# oresat-proto-card-7.net
KiCad netlist of a schematic drawn in EAGLE
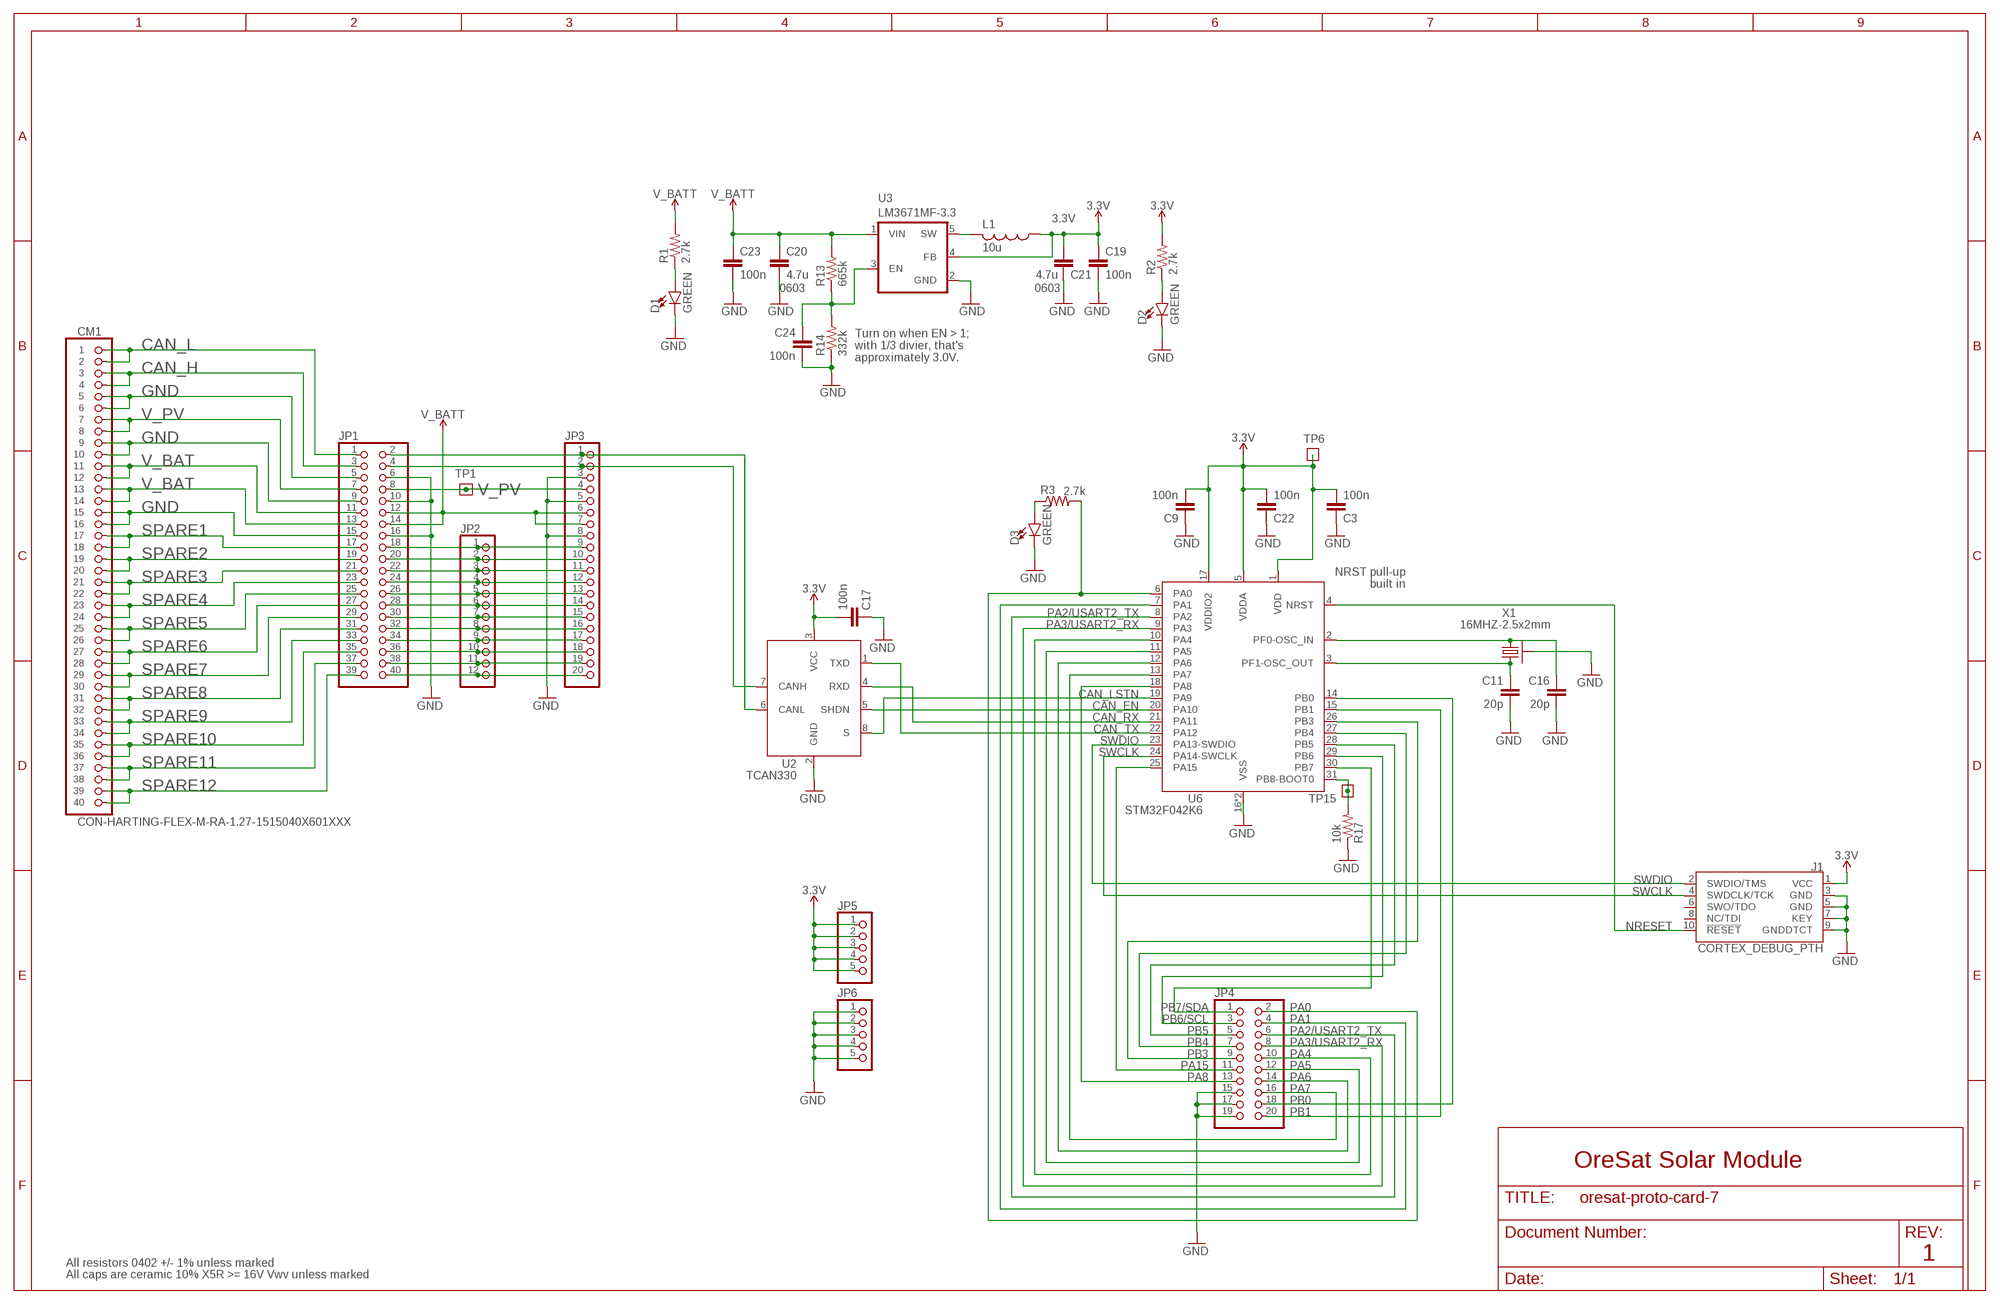
[diagram p0: schematic, sheet 1]

(export (version "E")
  (design (tool "Eeschema 10.0.6"))
  (components
    (comp (ref "C3")
      (value "100n")
      (footprint "eagle-import:.0402-B-NOSILK")
      (fields (field (name "MFR") "Samsung") (field (name "MPN") "CL05B104KO5NNNC"))
      (libsource (lib "eagle-import") (part "C-EU0402-B-NOSILK"))
    )
    (comp (ref "C9")
      (value "100n")
      (footprint "eagle-import:.0402-B-NOSILK")
      (fields (field (name "MFR") "Samsung") (field (name "MPN") "CL05B104KO5NNNC"))
      (libsource (lib "eagle-import") (part "C-EU0402-B-NOSILK"))
    )
    (comp (ref "C11")
      (value "20p")
      (footprint "eagle-import:.0402-B-NOSILK")
      (fields (field (name "MFR") "Samsung") (field (name "MPN") "CL05C200JB51PNC"))
      (libsource (lib "eagle-import") (part "C-EU0402-B-NOSILK"))
    )
    (comp (ref "C16")
      (value "20p")
      (footprint "eagle-import:.0402-B-NOSILK")
      (fields (field (name "MFR") "Samsung") (field (name "MPN") "CL05C200JB51PNC"))
      (libsource (lib "eagle-import") (part "C-EU0402-B-NOSILK"))
    )
    (comp (ref "C17")
      (value "100n")
      (footprint "eagle-import:.0402-B-NOSILK")
      (fields (field (name "MFR") "Samsung") (field (name "MPN") "CL05B104KO5NNNC"))
      (libsource (lib "eagle-import") (part "C-EU0402-B-NOSILK"))
    )
    (comp (ref "C19")
      (value "100n")
      (footprint "eagle-import:.0402-B-NOSILK")
      (fields (field (name "MFR") "Samsung") (field (name "MPN") "CL05B104KO5NNNC"))
      (libsource (lib "eagle-import") (part "C-EU0402-B-NOSILK"))
    )
    (comp (ref "C20")
      (value "4.7u")
      (footprint "eagle-import:C0603")
      (fields (field (name "MFR") "Samsung") (field (name "MPN") "CL05B104KO5NNNC"))
      (libsource (lib "eagle-import") (part "C-EUC0603"))
    )
    (comp (ref "C21")
      (value "4.7u")
      (footprint "eagle-import:C0603")
      (fields (field (name "MFR") "Samsung") (field (name "MPN") "CL05B104KO5NNNC"))
      (libsource (lib "eagle-import") (part "C-EUC0603"))
    )
    (comp (ref "C22")
      (value "100n")
      (footprint "eagle-import:.0402-B-NOSILK")
      (fields (field (name "MFR") "Samsung") (field (name "MPN") "CL05B104KO5NNNC"))
      (libsource (lib "eagle-import") (part "C-EU0402-B-NOSILK"))
    )
    (comp (ref "C23")
      (value "100n")
      (footprint "eagle-import:.0402-B-NOSILK")
      (fields (field (name "MFR") "Samsung") (field (name "MPN") "CL05B104KO5NNNC"))
      (libsource (lib "eagle-import") (part "C-EU0402-B-NOSILK"))
    )
    (comp (ref "C24")
      (value "100n")
      (footprint "eagle-import:.0402-B-NOSILK")
      (fields (field (name "MFR") "Samsung") (field (name "MPN") "CL05B104KO5NNNC"))
      (libsource (lib "eagle-import") (part "C-EU0402-B-NOSILK"))
    )
    (comp (ref "CM1")
      (value "CON-HARTING-FLEX-M-RA-1.27-1515040X601XXX")
      (footprint "eagle-import:CON-1.27-M-RA-HARTING-1515040X601XXX")
      (libsource (lib "eagle-import") (part "CON-HARTING-FLEX-M-RA-1.27-1515040X601XXX"))
    )
    (comp (ref "D1")
      (value "GREEN")
      (footprint "eagle-import:LED-0603")
      (libsource (lib "eagle-import") (part "LED-GREEN0603"))
    )
    (comp (ref "D2")
      (value "GREEN")
      (footprint "eagle-import:LED-0603")
      (libsource (lib "eagle-import") (part "LED-GREEN0603"))
    )
    (comp (ref "D3")
      (value "GREEN")
      (footprint "eagle-import:LED-0603")
      (libsource (lib "eagle-import") (part "LED-GREEN0603"))
    )
    (comp (ref "J1")
      (value "CORTEX_DEBUG_PTH")
      (footprint "eagle-import:2X5-PTH-1.27MM")
      (libsource (lib "eagle-import") (part "CORTEX_DEBUG_PTH"))
    )
    (comp (ref "JP1")
      (value "PINHD-2X20")
      (footprint "eagle-import:2X20")
      (libsource (lib "eagle-import") (part "PINHD-2X20"))
    )
    (comp (ref "JP2")
      (value "PINHD-1X12")
      (footprint "eagle-import:1X12")
      (libsource (lib "eagle-import") (part "PINHD-1X12"))
    )
    (comp (ref "JP3")
      (value "PINHD-1X20")
      (footprint "eagle-import:1X20")
      (libsource (lib "eagle-import") (part "PINHD-1X20"))
    )
    (comp (ref "JP4")
      (value "PINHD-2X10")
      (footprint "eagle-import:2X10")
      (libsource (lib "eagle-import") (part "PINHD-2X10"))
    )
    (comp (ref "JP5")
      (value "PINHD-1X5")
      (footprint "eagle-import:1X05")
      (libsource (lib "eagle-import") (part "PINHD-1X5"))
    )
    (comp (ref "JP6")
      (value "PINHD-1X5")
      (footprint "eagle-import:1X05")
      (libsource (lib "eagle-import") (part "PINHD-1X5"))
    )
    (comp (ref "L1")
      (value "10u")
      (footprint "eagle-import:L2012C")
      (fields (field (name "MFR") "Taiyo Yuden") (field (name "MPN") "CB2012T100KR"))
      (libsource (lib "eagle-import") (part "L-USL2012C"))
    )
    (comp (ref "R1")
      (value "2.7k")
      (footprint "eagle-import:.0402-B-NOSILK")
      (fields (field (name "MFR") "Samsung") (field (name "MPN") "RC1005F6653CS"))
      (libsource (lib "eagle-import") (part "R-US_0402-B-NOSILK"))
    )
    (comp (ref "R2")
      (value "2.7k")
      (footprint "eagle-import:.0402-B-NOSILK")
      (fields (field (name "MFR") "Samsung") (field (name "MPN") "RC1005F6653CS"))
      (libsource (lib "eagle-import") (part "R-US_0402-B-NOSILK"))
    )
    (comp (ref "R3")
      (value "2.7k")
      (footprint "eagle-import:.0402-B-NOSILK")
      (fields (field (name "MFR") "Samsung") (field (name "MPN") "RC1005F6653CS"))
      (libsource (lib "eagle-import") (part "R-US_0402-B-NOSILK"))
    )
    (comp (ref "R13")
      (value "665k")
      (footprint "eagle-import:.0402-B-NOSILK")
      (fields (field (name "MFR") "Samsung") (field (name "MPN") "RC1005F6653CS"))
      (libsource (lib "eagle-import") (part "R-US_0402-B-NOSILK"))
    )
    (comp (ref "R14")
      (value "332k")
      (footprint "eagle-import:.0402-B-NOSILK")
      (fields (field (name "MFR") "Samsung") (field (name "MPN") "RC1005F3323CS"))
      (libsource (lib "eagle-import") (part "R-US_0402-B-NOSILK"))
    )
    (comp (ref "R17")
      (value "10k")
      (footprint "eagle-import:.0402-B-NOSILK")
      (fields (field (name "MFR") "Samsung") (field (name "MPN") "RC1005F6653CS"))
      (libsource (lib "eagle-import") (part "R-US_0402-B-NOSILK"))
    )
    (comp (ref "TP1")
      (value "TEST-POINT")
      (footprint "eagle-import:2MM-TEST-POINT")
      (libsource (lib "eagle-import") (part "TEST-POINT"))
    )
    (comp (ref "TP6")
      (value "TEST-POINT")
      (footprint "eagle-import:2MM-TEST-POINT")
      (libsource (lib "eagle-import") (part "TEST-POINT"))
    )
    (comp (ref "TP15")
      (value "TEST-POINT")
      (footprint "eagle-import:2MM-TEST-POINT")
      (libsource (lib "eagle-import") (part "TEST-POINT"))
    )
    (comp (ref "U2")
      (value "TCAN330")
      (footprint "eagle-import:SOT23-8_TI-DCN")
      (fields (field (name "MFR") "Texas Instruments") (field (name "MPN") "TCAN330GDCNT"))
      (libsource (lib "eagle-import") (part "TCAN330"))
    )
    (comp (ref "U3")
      (value "LM3671MF-3.3")
      (footprint "eagle-import:SOT23-5")
      (fields (field (name "MFR") "TI") (field (name "MPN") "LM3671MF-3.3/NOPB"))
      (libsource (lib "eagle-import") (part "LM3761"))
    )
    (comp (ref "U6")
      (value "STM32F042K6")
      (footprint "eagle-import:QFP32-7X7")
      (fields (field (name "MFR") "STMicroelectronics") (field (name "MPN") "STM32F042K6T7"))
      (libsource (lib "eagle-import") (part "STM32F042K6"))
    )
    (comp (ref "X1")
      (value "16MHZ-2.5x2mm")
      (footprint "eagle-import:CRYSTAL_2.5X2")
      (fields (field (name "MFR") "ECS Inc.") (field (name "MPN") "ECS-160-10-36Q-ES-TR"))
      (libsource (lib "eagle-import") (part "CRYSTAL-WITH-GND"))
    )
  )
  (nets
    (net (code "1") (name "/CAN_EN") (class "Default")
      (node (ref "U2") (pin "5") (pinfunction "SHDN_5") (pintype "input"))
      (node (ref "U6") (pin "20") (pinfunction "PA10_20") (pintype "bidirectional"))
    )
    (net (code "2") (name "/CAN_H") (class "Default")
      (node (ref "CM1") (pin "3") (pinfunction "3_3") (pintype "passive"))
      (node (ref "CM1") (pin "4") (pinfunction "4_4") (pintype "passive"))
      (node (ref "JP1") (pin "3") (pinfunction "3_3") (pintype "passive"))
    )
    (net (code "3") (name "/CAN_L") (class "Default")
      (node (ref "CM1") (pin "1") (pinfunction "1_1") (pintype "passive"))
      (node (ref "CM1") (pin "2") (pinfunction "2_2") (pintype "passive"))
      (node (ref "JP1") (pin "1") (pinfunction "1_1") (pintype "passive"))
    )
    (net (code "4") (name "/CAN_LSTN") (class "Default")
      (node (ref "U2") (pin "8") (pinfunction "S_8") (pintype "input"))
      (node (ref "U6") (pin "19") (pinfunction "PA9_19") (pintype "bidirectional"))
    )
    (net (code "5") (name "/CAN_RX") (class "Default")
      (node (ref "U2") (pin "4") (pinfunction "RXD_4") (pintype "output"))
      (node (ref "U6") (pin "21") (pinfunction "PA11_21") (pintype "bidirectional"))
    )
    (net (code "6") (name "/CAN_TX") (class "Default")
      (node (ref "U2") (pin "1") (pinfunction "TXD_1") (pintype "input"))
      (node (ref "U6") (pin "22") (pinfunction "PA12_22") (pintype "bidirectional"))
    )
    (net (code "7") (name "/NRESET") (class "Default")
      (node (ref "J1") (pin "10") (pinfunction "~{RESET}_10") (pintype "bidirectional"))
      (node (ref "U6") (pin "4") (pinfunction "NRST_4") (pintype "bidirectional"))
    )
    (net (code "8") (name "/PA0") (class "Default")
      (node (ref "JP4") (pin "2") (pinfunction "2_2") (pintype "passive"))
      (node (ref "R3") (pin "2") (pinfunction "2_2") (pintype "passive"))
      (node (ref "U6") (pin "6") (pinfunction "PA0_6") (pintype "bidirectional"))
    )
    (net (code "9") (name "/PA1") (class "Default")
      (node (ref "JP4") (pin "4") (pinfunction "4_4") (pintype "passive"))
      (node (ref "U6") (pin "7") (pinfunction "PA1_7") (pintype "bidirectional"))
    )
    (net (code "10") (name "/PA2{slash}USART2_TX") (class "Default")
      (node (ref "JP4") (pin "6") (pinfunction "6_6") (pintype "passive"))
      (node (ref "U6") (pin "8") (pinfunction "PA2_8") (pintype "bidirectional"))
    )
    (net (code "11") (name "/PA3{slash}USART2_RX") (class "Default")
      (node (ref "JP4") (pin "8") (pinfunction "8_8") (pintype "passive"))
      (node (ref "U6") (pin "9") (pinfunction "PA3_9") (pintype "bidirectional"))
    )
    (net (code "12") (name "/PA4") (class "Default")
      (node (ref "JP4") (pin "10") (pinfunction "10_10") (pintype "passive"))
      (node (ref "U6") (pin "10") (pinfunction "PA4_10") (pintype "bidirectional"))
    )
    (net (code "13") (name "/PA5") (class "Default")
      (node (ref "JP4") (pin "12") (pinfunction "12_12") (pintype "passive"))
      (node (ref "U6") (pin "11") (pinfunction "PA5_11") (pintype "bidirectional"))
    )
    (net (code "14") (name "/PA6") (class "Default")
      (node (ref "JP4") (pin "14") (pinfunction "14_14") (pintype "passive"))
      (node (ref "U6") (pin "12") (pinfunction "PA6_12") (pintype "bidirectional"))
    )
    (net (code "15") (name "/PA7") (class "Default")
      (node (ref "JP4") (pin "16") (pinfunction "16_16") (pintype "passive"))
      (node (ref "U6") (pin "13") (pinfunction "PA7_13") (pintype "bidirectional"))
    )
    (net (code "16") (name "/PA8") (class "Default")
      (node (ref "JP4") (pin "13") (pinfunction "13_13") (pintype "passive"))
      (node (ref "U6") (pin "18") (pinfunction "PA8_18") (pintype "bidirectional"))
    )
    (net (code "17") (name "/PA15") (class "Default")
      (node (ref "JP4") (pin "11") (pinfunction "11_11") (pintype "passive"))
      (node (ref "U6") (pin "25") (pinfunction "PA15_25") (pintype "bidirectional"))
    )
    (net (code "18") (name "/PB0") (class "Default")
      (node (ref "JP4") (pin "18") (pinfunction "18_18") (pintype "passive"))
      (node (ref "U6") (pin "14") (pinfunction "PB0_14") (pintype "bidirectional"))
    )
    (net (code "19") (name "/PB1") (class "Default")
      (node (ref "JP4") (pin "20") (pinfunction "20_20") (pintype "passive"))
      (node (ref "U6") (pin "15") (pinfunction "PB1_15") (pintype "bidirectional"))
    )
    (net (code "20") (name "/PB3") (class "Default")
      (node (ref "JP4") (pin "9") (pinfunction "9_9") (pintype "passive"))
      (node (ref "U6") (pin "26") (pinfunction "PB3_26") (pintype "bidirectional"))
    )
    (net (code "21") (name "/PB4") (class "Default")
      (node (ref "JP4") (pin "7") (pinfunction "7_7") (pintype "passive"))
      (node (ref "U6") (pin "27") (pinfunction "PB4_27") (pintype "bidirectional"))
    )
    (net (code "22") (name "/PB5") (class "Default")
      (node (ref "JP4") (pin "5") (pinfunction "5_5") (pintype "passive"))
      (node (ref "U6") (pin "28") (pinfunction "PB5_28") (pintype "bidirectional"))
    )
    (net (code "23") (name "/PB6{slash}SCL") (class "Default")
      (node (ref "JP4") (pin "3") (pinfunction "3_3") (pintype "passive"))
      (node (ref "U6") (pin "29") (pinfunction "PB6_29") (pintype "bidirectional"))
    )
    (net (code "24") (name "/PB7{slash}SDA") (class "Default")
      (node (ref "JP4") (pin "1") (pinfunction "1_1") (pintype "passive"))
      (node (ref "U6") (pin "30") (pinfunction "PB7_30") (pintype "bidirectional"))
    )
    (net (code "25") (name "/SPARE1") (class "Default")
      (node (ref "CM1") (pin "17") (pinfunction "17_17") (pintype "passive"))
      (node (ref "CM1") (pin "18") (pinfunction "18_18") (pintype "passive"))
      (node (ref "JP1") (pin "17") (pinfunction "17_17") (pintype "passive"))
    )
    (net (code "26") (name "/SPARE2") (class "Default")
      (node (ref "CM1") (pin "19") (pinfunction "19_19") (pintype "passive"))
      (node (ref "CM1") (pin "20") (pinfunction "20_20") (pintype "passive"))
      (node (ref "JP1") (pin "19") (pinfunction "19_19") (pintype "passive"))
    )
    (net (code "27") (name "/SPARE3") (class "Default")
      (node (ref "CM1") (pin "21") (pinfunction "21_21") (pintype "passive"))
      (node (ref "CM1") (pin "22") (pinfunction "22_22") (pintype "passive"))
      (node (ref "JP1") (pin "21") (pinfunction "21_21") (pintype "passive"))
    )
    (net (code "28") (name "/SPARE4") (class "Default")
      (node (ref "CM1") (pin "23") (pinfunction "23_23") (pintype "passive"))
      (node (ref "CM1") (pin "24") (pinfunction "24_24") (pintype "passive"))
      (node (ref "JP1") (pin "23") (pinfunction "23_23") (pintype "passive"))
    )
    (net (code "29") (name "/SPARE5") (class "Default")
      (node (ref "CM1") (pin "25") (pinfunction "25_25") (pintype "passive"))
      (node (ref "CM1") (pin "26") (pinfunction "26_26") (pintype "passive"))
      (node (ref "JP1") (pin "25") (pinfunction "25_25") (pintype "passive"))
    )
    (net (code "30") (name "/SPARE6") (class "Default")
      (node (ref "CM1") (pin "27") (pinfunction "27_27") (pintype "passive"))
      (node (ref "CM1") (pin "28") (pinfunction "28_28") (pintype "passive"))
      (node (ref "JP1") (pin "27") (pinfunction "27_27") (pintype "passive"))
    )
    (net (code "31") (name "/SPARE7") (class "Default")
      (node (ref "CM1") (pin "29") (pinfunction "29_29") (pintype "passive"))
      (node (ref "CM1") (pin "30") (pinfunction "30_30") (pintype "passive"))
      (node (ref "JP1") (pin "29") (pinfunction "29_29") (pintype "passive"))
    )
    (net (code "32") (name "/SPARE8") (class "Default")
      (node (ref "CM1") (pin "31") (pinfunction "31_31") (pintype "passive"))
      (node (ref "CM1") (pin "32") (pinfunction "32_32") (pintype "passive"))
      (node (ref "JP1") (pin "31") (pinfunction "31_31") (pintype "passive"))
    )
    (net (code "33") (name "/SPARE9") (class "Default")
      (node (ref "CM1") (pin "33") (pinfunction "33_33") (pintype "passive"))
      (node (ref "CM1") (pin "34") (pinfunction "34_34") (pintype "passive"))
      (node (ref "JP1") (pin "33") (pinfunction "33_33") (pintype "passive"))
    )
    (net (code "34") (name "/SPARE10") (class "Default")
      (node (ref "CM1") (pin "35") (pinfunction "35_35") (pintype "passive"))
      (node (ref "CM1") (pin "36") (pinfunction "36_36") (pintype "passive"))
      (node (ref "JP1") (pin "35") (pinfunction "35_35") (pintype "passive"))
    )
    (net (code "35") (name "/SPARE11") (class "Default")
      (node (ref "CM1") (pin "37") (pinfunction "37_37") (pintype "passive"))
      (node (ref "CM1") (pin "38") (pinfunction "38_38") (pintype "passive"))
      (node (ref "JP1") (pin "37") (pinfunction "37_37") (pintype "passive"))
    )
    (net (code "36") (name "/SPARE12") (class "Default")
      (node (ref "CM1") (pin "39") (pinfunction "39_39") (pintype "passive"))
      (node (ref "CM1") (pin "40") (pinfunction "40_40") (pintype "passive"))
      (node (ref "JP1") (pin "39") (pinfunction "39_39") (pintype "passive"))
    )
    (net (code "37") (name "/SWCLK") (class "Default")
      (node (ref "J1") (pin "4") (pinfunction "SWDCLK/TCK_4") (pintype "bidirectional"))
      (node (ref "U6") (pin "24") (pinfunction "PA14-SWCLK_24") (pintype "bidirectional"))
    )
    (net (code "38") (name "/SWDIO") (class "Default")
      (node (ref "J1") (pin "2") (pinfunction "SWDIO/TMS_2") (pintype "bidirectional"))
      (node (ref "U6") (pin "23") (pinfunction "PA13-SWDIO_23") (pintype "bidirectional"))
    )
    (net (code "39") (name "/V_BAT") (class "Default")
      (node (ref "CM1") (pin "11") (pinfunction "11_11") (pintype "passive"))
      (node (ref "CM1") (pin "12") (pinfunction "12_12") (pintype "passive"))
      (node (ref "CM1") (pin "13") (pinfunction "13_13") (pintype "passive"))
      (node (ref "CM1") (pin "14") (pinfunction "14_14") (pintype "passive"))
      (node (ref "JP1") (pin "11") (pinfunction "11_11") (pintype "passive"))
      (node (ref "JP1") (pin "13") (pinfunction "13_13") (pintype "passive"))
    )
    (net (code "40") (name "/V_PV") (class "Default")
      (node (ref "CM1") (pin "7") (pinfunction "7_7") (pintype "passive"))
      (node (ref "CM1") (pin "8") (pinfunction "8_8") (pintype "passive"))
      (node (ref "JP1") (pin "7") (pinfunction "7_7") (pintype "passive"))
    )
    (net (code "41") (name "3.3V") (class "Default")
      (node (ref "C17") (pin "2") (pinfunction "2_2") (pintype "passive"))
      (node (ref "C19") (pin "1") (pinfunction "1_1") (pintype "passive"))
      (node (ref "C21") (pin "1") (pinfunction "1_1") (pintype "passive"))
      (node (ref "C22") (pin "2") (pinfunction "2_2") (pintype "passive"))
      (node (ref "C3") (pin "2") (pinfunction "2_2") (pintype "passive"))
      (node (ref "C9") (pin "2") (pinfunction "2_2") (pintype "passive"))
      (node (ref "J1") (pin "1") (pinfunction "VCC_1") (pintype "bidirectional"))
      (node (ref "JP5") (pin "1") (pinfunction "1_1") (pintype "passive"))
      (node (ref "JP5") (pin "2") (pinfunction "2_2") (pintype "passive"))
      (node (ref "JP5") (pin "3") (pinfunction "3_3") (pintype "passive"))
      (node (ref "JP5") (pin "4") (pinfunction "4_4") (pintype "passive"))
      (node (ref "JP5") (pin "5") (pinfunction "5_5") (pintype "passive"))
      (node (ref "L1") (pin "1") (pinfunction "1_1") (pintype "passive"))
      (node (ref "R2") (pin "2") (pinfunction "2_2") (pintype "passive"))
      (node (ref "TP6") (pin "1") (pinfunction "1_1") (pintype "passive"))
      (node (ref "U2") (pin "3") (pinfunction "VCC_3") (pintype "power_in"))
      (node (ref "U3") (pin "4") (pinfunction "FB_4") (pintype "input"))
      (node (ref "U6") (pin "1") (pinfunction "VDD_1") (pintype "power_in"))
      (node (ref "U6") (pin "17") (pinfunction "VDDIO2_17") (pintype "power_in"))
      (node (ref "U6") (pin "5") (pinfunction "VDDA_5") (pintype "power_in"))
    )
    (net (code "42") (name "GND") (class "Default")
      (node (ref "C11") (pin "2") (pinfunction "2_2") (pintype "passive"))
      (node (ref "C16") (pin "2") (pinfunction "2_2") (pintype "passive"))
      (node (ref "C17") (pin "1") (pinfunction "1_1") (pintype "passive"))
      (node (ref "C19") (pin "2") (pinfunction "2_2") (pintype "passive"))
      (node (ref "C20") (pin "2") (pinfunction "2_2") (pintype "passive"))
      (node (ref "C21") (pin "2") (pinfunction "2_2") (pintype "passive"))
      (node (ref "C22") (pin "1") (pinfunction "1_1") (pintype "passive"))
      (node (ref "C23") (pin "2") (pinfunction "2_2") (pintype "passive"))
      (node (ref "C24") (pin "2") (pinfunction "2_2") (pintype "passive"))
      (node (ref "C3") (pin "1") (pinfunction "1_1") (pintype "passive"))
      (node (ref "C9") (pin "1") (pinfunction "1_1") (pintype "passive"))
      (node (ref "CM1") (pin "10") (pinfunction "10_10") (pintype "passive"))
      (node (ref "CM1") (pin "15") (pinfunction "15_15") (pintype "passive"))
      (node (ref "CM1") (pin "16") (pinfunction "16_16") (pintype "passive"))
      (node (ref "CM1") (pin "5") (pinfunction "5_5") (pintype "passive"))
      (node (ref "CM1") (pin "6") (pinfunction "6_6") (pintype "passive"))
      (node (ref "CM1") (pin "9") (pinfunction "9_9") (pintype "passive"))
      (node (ref "D1") (pin "C") (pinfunction "C_C") (pintype "passive"))
      (node (ref "D2") (pin "C") (pinfunction "C_C") (pintype "passive"))
      (node (ref "D3") (pin "C") (pinfunction "C_C") (pintype "passive"))
      (node (ref "J1") (pin "3") (pinfunction "GND_3") (pintype "bidirectional"))
      (node (ref "J1") (pin "5") (pinfunction "GND_5") (pintype "bidirectional"))
      (node (ref "J1") (pin "7") (pinfunction "KEY_7") (pintype "bidirectional"))
      (node (ref "J1") (pin "9") (pinfunction "GNDDTCT_9") (pintype "bidirectional"))
      (node (ref "JP1") (pin "10") (pinfunction "10_10") (pintype "passive"))
      (node (ref "JP1") (pin "15") (pinfunction "15_15") (pintype "passive"))
      (node (ref "JP1") (pin "16") (pinfunction "16_16") (pintype "passive"))
      (node (ref "JP1") (pin "5") (pinfunction "5_5") (pintype "passive"))
      (node (ref "JP1") (pin "6") (pinfunction "6_6") (pintype "passive"))
      (node (ref "JP1") (pin "9") (pinfunction "9_9") (pintype "passive"))
      (node (ref "JP3") (pin "3") (pinfunction "3_3") (pintype "passive"))
      (node (ref "JP3") (pin "5") (pinfunction "5_5") (pintype "passive"))
      (node (ref "JP3") (pin "8") (pinfunction "8_8") (pintype "passive"))
      (node (ref "JP4") (pin "15") (pinfunction "15_15") (pintype "passive"))
      (node (ref "JP4") (pin "17") (pinfunction "17_17") (pintype "passive"))
      (node (ref "JP4") (pin "19") (pinfunction "19_19") (pintype "passive"))
      (node (ref "JP6") (pin "1") (pinfunction "1_1") (pintype "passive"))
      (node (ref "JP6") (pin "2") (pinfunction "2_2") (pintype "passive"))
      (node (ref "JP6") (pin "3") (pinfunction "3_3") (pintype "passive"))
      (node (ref "JP6") (pin "4") (pinfunction "4_4") (pintype "passive"))
      (node (ref "JP6") (pin "5") (pinfunction "5_5") (pintype "passive"))
      (node (ref "R14") (pin "1") (pinfunction "1_1") (pintype "passive"))
      (node (ref "R17") (pin "1") (pinfunction "1_1") (pintype "passive"))
      (node (ref "U2") (pin "2") (pinfunction "GND_2") (pintype "power_in"))
      (node (ref "U3") (pin "2") (pinfunction "GND_2") (pintype "bidirectional"))
      (node (ref "U6") (pin "16") (pinfunction "VSS_16") (pintype "power_in"))
      (node (ref "U6") (pin "32") (pinfunction "VSS_32") (pintype "power_in"))
      (node (ref "X1") (pin "2") (pinfunction "SHIELD_2") (pintype "power_in"))
      (node (ref "X1") (pin "4") (pinfunction "SHIELD_4") (pintype "power_in"))
    )
    (net (code "43") (name "Net-(D1-PadA)") (class "Default")
      (node (ref "D1") (pin "A") (pinfunction "A_A") (pintype "passive"))
      (node (ref "R1") (pin "1") (pinfunction "1_1") (pintype "passive"))
    )
    (net (code "44") (name "Net-(D2-PadA)") (class "Default")
      (node (ref "D2") (pin "A") (pinfunction "A_A") (pintype "passive"))
      (node (ref "R2") (pin "1") (pinfunction "1_1") (pintype "passive"))
    )
    (net (code "45") (name "Net-(D3-PadA)") (class "Default")
      (node (ref "D3") (pin "A") (pinfunction "A_A") (pintype "passive"))
      (node (ref "R3") (pin "1") (pinfunction "1_1") (pintype "passive"))
    )
    (net (code "46") (name "Net-(JP1-Pad8)") (class "Default")
      (node (ref "JP1") (pin "8") (pinfunction "8_8") (pintype "passive"))
      (node (ref "JP3") (pin "4") (pinfunction "4_4") (pintype "passive"))
      (node (ref "TP1") (pin "1") (pinfunction "1_1") (pintype "passive"))
    )
    (net (code "47") (name "Net-(JP1-Pad18)") (class "Default")
      (node (ref "JP1") (pin "18") (pinfunction "18_18") (pintype "passive"))
      (node (ref "JP2") (pin "1") (pinfunction "1_1") (pintype "passive"))
      (node (ref "JP3") (pin "9") (pinfunction "9_9") (pintype "passive"))
    )
    (net (code "48") (name "Net-(JP1-Pad20)") (class "Default")
      (node (ref "JP1") (pin "20") (pinfunction "20_20") (pintype "passive"))
      (node (ref "JP2") (pin "2") (pinfunction "2_2") (pintype "passive"))
      (node (ref "JP3") (pin "10") (pinfunction "10_10") (pintype "passive"))
    )
    (net (code "49") (name "Net-(JP1-Pad22)") (class "Default")
      (node (ref "JP1") (pin "22") (pinfunction "22_22") (pintype "passive"))
      (node (ref "JP2") (pin "3") (pinfunction "3_3") (pintype "passive"))
      (node (ref "JP3") (pin "11") (pinfunction "11_11") (pintype "passive"))
    )
    (net (code "50") (name "Net-(JP1-Pad24)") (class "Default")
      (node (ref "JP1") (pin "24") (pinfunction "24_24") (pintype "passive"))
      (node (ref "JP2") (pin "4") (pinfunction "4_4") (pintype "passive"))
      (node (ref "JP3") (pin "12") (pinfunction "12_12") (pintype "passive"))
    )
    (net (code "51") (name "Net-(JP1-Pad26)") (class "Default")
      (node (ref "JP1") (pin "26") (pinfunction "26_26") (pintype "passive"))
      (node (ref "JP2") (pin "5") (pinfunction "5_5") (pintype "passive"))
      (node (ref "JP3") (pin "13") (pinfunction "13_13") (pintype "passive"))
    )
    (net (code "52") (name "Net-(JP1-Pad28)") (class "Default")
      (node (ref "JP1") (pin "28") (pinfunction "28_28") (pintype "passive"))
      (node (ref "JP2") (pin "6") (pinfunction "6_6") (pintype "passive"))
      (node (ref "JP3") (pin "14") (pinfunction "14_14") (pintype "passive"))
    )
    (net (code "53") (name "Net-(JP1-Pad30)") (class "Default")
      (node (ref "JP1") (pin "30") (pinfunction "30_30") (pintype "passive"))
      (node (ref "JP2") (pin "7") (pinfunction "7_7") (pintype "passive"))
      (node (ref "JP3") (pin "15") (pinfunction "15_15") (pintype "passive"))
    )
    (net (code "54") (name "Net-(JP1-Pad32)") (class "Default")
      (node (ref "JP1") (pin "32") (pinfunction "32_32") (pintype "passive"))
      (node (ref "JP2") (pin "8") (pinfunction "8_8") (pintype "passive"))
      (node (ref "JP3") (pin "16") (pinfunction "16_16") (pintype "passive"))
    )
    (net (code "55") (name "Net-(JP1-Pad34)") (class "Default")
      (node (ref "JP1") (pin "34") (pinfunction "34_34") (pintype "passive"))
      (node (ref "JP2") (pin "9") (pinfunction "9_9") (pintype "passive"))
      (node (ref "JP3") (pin "17") (pinfunction "17_17") (pintype "passive"))
    )
    (net (code "56") (name "Net-(JP1-Pad36)") (class "Default")
      (node (ref "JP1") (pin "36") (pinfunction "36_36") (pintype "passive"))
      (node (ref "JP2") (pin "10") (pinfunction "10_10") (pintype "passive"))
      (node (ref "JP3") (pin "18") (pinfunction "18_18") (pintype "passive"))
    )
    (net (code "57") (name "Net-(JP1-Pad38)") (class "Default")
      (node (ref "JP1") (pin "38") (pinfunction "38_38") (pintype "passive"))
      (node (ref "JP2") (pin "11") (pinfunction "11_11") (pintype "passive"))
      (node (ref "JP3") (pin "19") (pinfunction "19_19") (pintype "passive"))
    )
    (net (code "58") (name "Net-(JP1-Pad40)") (class "Default")
      (node (ref "JP1") (pin "40") (pinfunction "40_40") (pintype "passive"))
      (node (ref "JP2") (pin "12") (pinfunction "12_12") (pintype "passive"))
      (node (ref "JP3") (pin "20") (pinfunction "20_20") (pintype "passive"))
    )
    (net (code "59") (name "Net-(U2-CANH)") (class "Default")
      (node (ref "JP1") (pin "4") (pinfunction "4_4") (pintype "passive"))
      (node (ref "JP3") (pin "2") (pinfunction "2_2") (pintype "passive"))
      (node (ref "U2") (pin "7") (pinfunction "CANH_7") (pintype "bidirectional"))
    )
    (net (code "60") (name "Net-(U2-CANL)") (class "Default")
      (node (ref "JP1") (pin "2") (pinfunction "2_2") (pintype "passive"))
      (node (ref "JP3") (pin "1") (pinfunction "1_1") (pintype "passive"))
      (node (ref "U2") (pin "6") (pinfunction "CANL_6") (pintype "bidirectional"))
    )
    (net (code "61") (name "Net-(U3-EN)") (class "Default")
      (node (ref "C24") (pin "1") (pinfunction "1_1") (pintype "passive"))
      (node (ref "R13") (pin "1") (pinfunction "1_1") (pintype "passive"))
      (node (ref "R14") (pin "2") (pinfunction "2_2") (pintype "passive"))
      (node (ref "U3") (pin "3") (pinfunction "EN_3") (pintype "input"))
    )
    (net (code "62") (name "Net-(U3-SW)") (class "Default")
      (node (ref "L1") (pin "2") (pinfunction "2_2") (pintype "passive"))
      (node (ref "U3") (pin "5") (pinfunction "SW_5") (pintype "bidirectional"))
    )
    (net (code "63") (name "Net-(U6-PB8-BOOT0)") (class "Default")
      (node (ref "R17") (pin "2") (pinfunction "2_2") (pintype "passive"))
      (node (ref "TP15") (pin "1") (pinfunction "1_1") (pintype "passive"))
      (node (ref "U6") (pin "31") (pinfunction "PB8-BOOT0_31") (pintype "bidirectional"))
    )
    (net (code "64") (name "Net-(U6-PF0-OSC_IN)") (class "Default")
      (node (ref "C16") (pin "1") (pinfunction "1_1") (pintype "passive"))
      (node (ref "U6") (pin "2") (pinfunction "PF0-OSC_IN_2") (pintype "bidirectional"))
      (node (ref "X1") (pin "1") (pinfunction "1_1") (pintype "passive"))
    )
    (net (code "65") (name "Net-(U6-PF1-OSC_OUT)") (class "Default")
      (node (ref "C11") (pin "1") (pinfunction "1_1") (pintype "passive"))
      (node (ref "U6") (pin "3") (pinfunction "PF1-OSC_OUT_3") (pintype "bidirectional"))
      (node (ref "X1") (pin "3") (pinfunction "2_3") (pintype "passive"))
    )
    (net (code "66") (name "V_BATT") (class "Default")
      (node (ref "C20") (pin "1") (pinfunction "1_1") (pintype "passive"))
      (node (ref "C23") (pin "1") (pinfunction "1_1") (pintype "passive"))
      (node (ref "JP1") (pin "12") (pinfunction "12_12") (pintype "passive"))
      (node (ref "JP1") (pin "14") (pinfunction "14_14") (pintype "passive"))
      (node (ref "JP3") (pin "6") (pinfunction "6_6") (pintype "passive"))
      (node (ref "JP3") (pin "7") (pinfunction "7_7") (pintype "passive"))
      (node (ref "R1") (pin "2") (pinfunction "2_2") (pintype "passive"))
      (node (ref "R13") (pin "2") (pinfunction "2_2") (pintype "passive"))
      (node (ref "U3") (pin "1") (pinfunction "VIN_1") (pintype "bidirectional"))
    )
    (net (code "67") (name "unconnected-(J1-NC{slash}TDI-Pad8)") (class "Default")
      (node (ref "J1") (pin "8") (pinfunction "NC/TDI_8") (pintype "bidirectional"))
    )
    (net (code "68") (name "unconnected-(J1-SWO{slash}TDO-Pad6)") (class "Default")
      (node (ref "J1") (pin "6") (pinfunction "SWO/TDO_6") (pintype "bidirectional"))
    )
  )
)
